# Power.net
KiCad netlist of a schematic drawn in Altium Designer
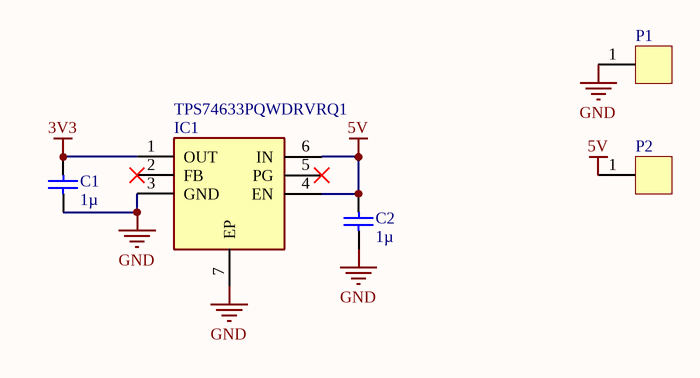
[diagram p0: Power.SchDoc]

(export (version "E")
  (design (tool "Eeschema 10.0.6"))
  (components
    (comp (ref "C1")
      (value "1µ")
      (footprint "CAPC0603(1608)55_N")
      (description "Keramikvielschichtkondensator, SMD, Baureihe MC, ± 20%")
      (fields (field (name "MANUFACTURER") "Multicomp"))
      (libsource (lib "Standardbauteile") (part "Cap 1µ"))
    )
    (comp (ref "C2")
      (value "1µ")
      (footprint "CAPC0603(1608)55_N")
      (description "Keramikvielschichtkondensator, SMD, Baureihe MC, ± 20%")
      (fields (field (name "MANUFACTURER") "Multicomp"))
      (libsource (lib "Standardbauteile") (part "Cap 1µ"))
    )
    (comp (ref "IC1")
      (value "TPS74633PQWDRVRQ1")
      (footprint "Custom Components:SON65P200X200X80-7N")
      (description "Integrated Circuit")
      (fields (field (name "MOUSER PART NUMBER") "595-PS74633PQWDRVRQ1"))
      (libsource (lib "*") (part "TPS74633PQWDRVRQ1"))
    )
    (comp (ref "P1")
      (value "solder pad square single sided")
      (footprint "solder pad single sided square")
      (libsource (lib "Custom Components") (part "solder pad square single sided"))
    )
    (comp (ref "P2")
      (value "solder pad chamfered single sided")
      (footprint "solder pad single sided chamfered")
      (libsource (lib "Custom Components") (part "solder pad chamfered single sided"))
    )
  )
  (nets
    (net (code "1") (name "3V3") (class "Default")
      (node (ref "C1") (pin "2") (pinfunction "2_2") (pintype "passive"))
      (node (ref "IC1") (pin "1") (pinfunction "OUT_1") (pintype "passive"))
    )
    (net (code "2") (name "5V") (class "Default")
      (node (ref "C2") (pin "2") (pinfunction "2_2") (pintype "passive"))
      (node (ref "IC1") (pin "4") (pinfunction "EN_4") (pintype "passive"))
      (node (ref "IC1") (pin "6") (pinfunction "IN_6") (pintype "passive"))
      (node (ref "P2") (pin "1") (pinfunction "upper_1") (pintype "passive"))
    )
    (net (code "3") (name "GND") (class "Default")
      (node (ref "C1") (pin "1") (pinfunction "1_1") (pintype "passive"))
      (node (ref "C2") (pin "1") (pinfunction "1_1") (pintype "passive"))
      (node (ref "IC1") (pin "3") (pinfunction "GND_3") (pintype "passive"))
      (node (ref "IC1") (pin "7") (pinfunction "EP_7") (pintype "passive"))
      (node (ref "P1") (pin "1") (pinfunction "upper_1") (pintype "passive"))
    )
    (net (code "4") (name "unconnected-(IC1-FB-Pad2)") (class "Default")
      (node (ref "IC1") (pin "2") (pinfunction "FB_2") (pintype "passive+no_connect"))
    )
    (net (code "5") (name "unconnected-(IC1-PG-Pad5)") (class "Default")
      (node (ref "IC1") (pin "5") (pinfunction "PG_5") (pintype "passive+no_connect"))
    )
  )
)
